# Rear_brake_lamp_v2.net
KiCad netlist of a schematic drawn in EAGLE
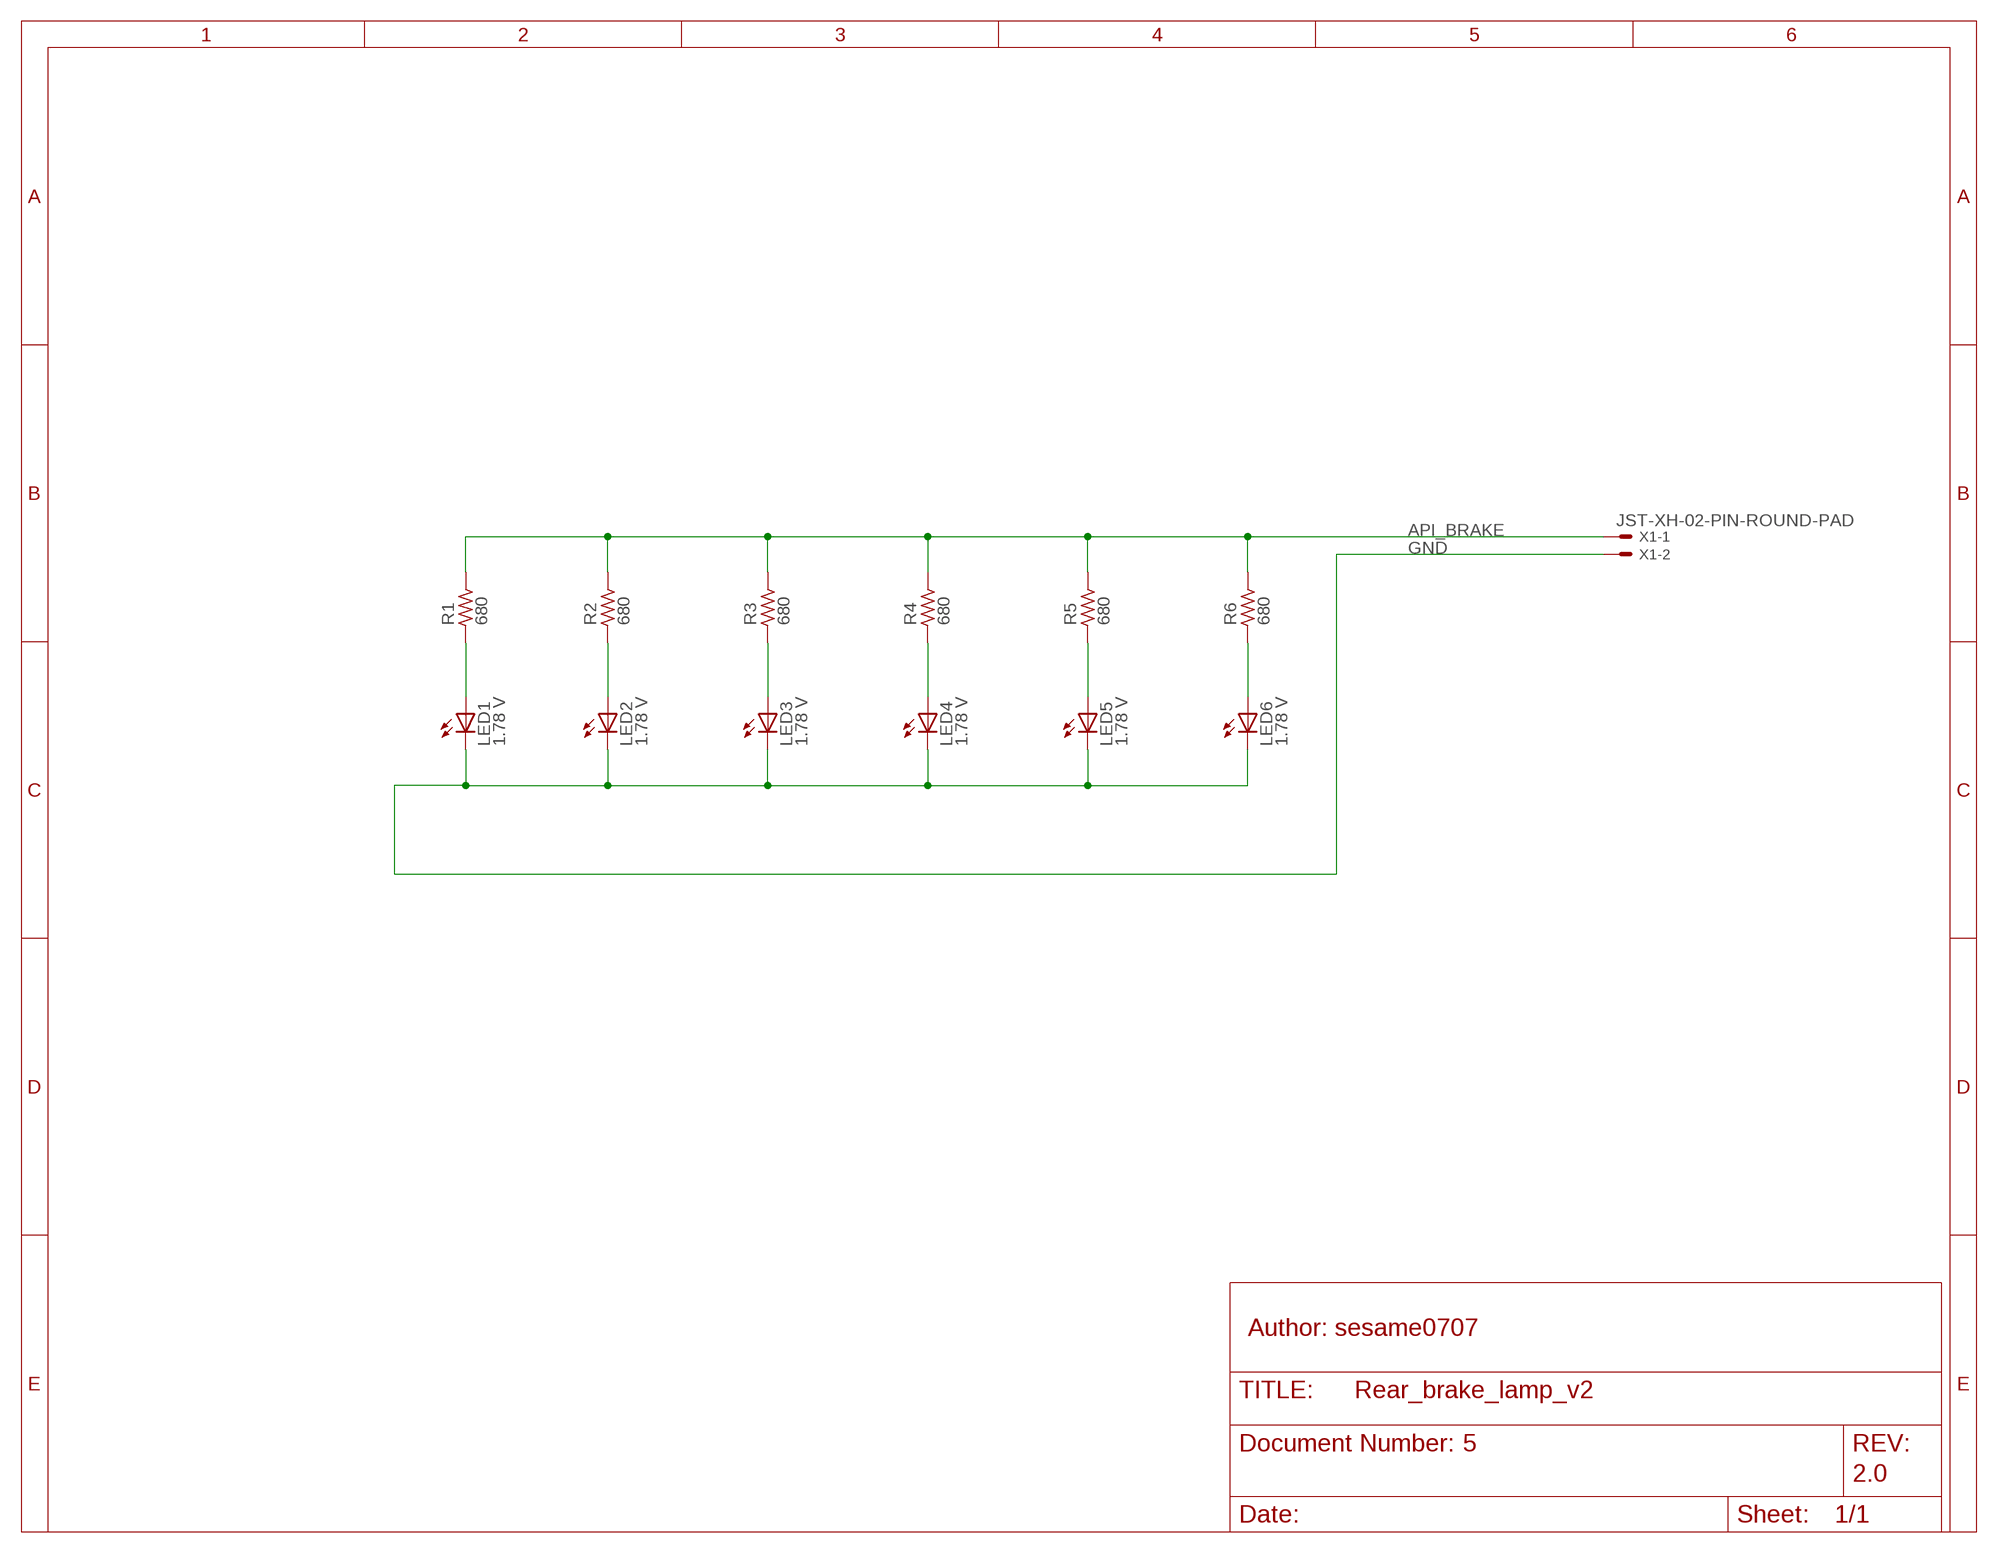
[diagram p0: schematic, sheet 1]

(export (version "E")
  (design (tool "Eeschema 10.0.6"))
  (components
    (comp (ref "LED1")
      (value "1.78 V")
      (footprint "eagle-import:LED5MM")
      (libsource (lib "eagle-import") (part "LED5MM"))
    )
    (comp (ref "LED2")
      (value "1.78 V")
      (footprint "eagle-import:LED5MM")
      (libsource (lib "eagle-import") (part "LED5MM"))
    )
    (comp (ref "LED3")
      (value "1.78 V")
      (footprint "eagle-import:LED5MM")
      (libsource (lib "eagle-import") (part "LED5MM"))
    )
    (comp (ref "LED4")
      (value "1.78 V")
      (footprint "eagle-import:LED5MM")
      (libsource (lib "eagle-import") (part "LED5MM"))
    )
    (comp (ref "LED5")
      (value "1.78 V")
      (footprint "eagle-import:LED5MM")
      (libsource (lib "eagle-import") (part "LED5MM"))
    )
    (comp (ref "LED6")
      (value "1.78 V")
      (footprint "eagle-import:LED5MM")
      (libsource (lib "eagle-import") (part "LED5MM"))
    )
    (comp (ref "R1")
      (value "680")
      (footprint "eagle-import:R0805")
      (libsource (lib "eagle-import") (part "R_0805"))
    )
    (comp (ref "R2")
      (value "680")
      (footprint "eagle-import:R0805")
      (libsource (lib "eagle-import") (part "R_0805"))
    )
    (comp (ref "R3")
      (value "680")
      (footprint "eagle-import:R0805")
      (libsource (lib "eagle-import") (part "R_0805"))
    )
    (comp (ref "R4")
      (value "680")
      (footprint "eagle-import:R0805")
      (libsource (lib "eagle-import") (part "R_0805"))
    )
    (comp (ref "R5")
      (value "680")
      (footprint "eagle-import:R0805")
      (libsource (lib "eagle-import") (part "R_0805"))
    )
    (comp (ref "R6")
      (value "680")
      (footprint "eagle-import:R0805")
      (libsource (lib "eagle-import") (part "R_0805"))
    )
    (comp (ref "X1")
      (value "JST-XH-02-PIN-ROUND-PAD")
      (footprint "eagle-import:JST-XH-02-PACKAGE-ROUND-PAD")
      (libsource (lib "eagle-import") (part "JST-XH-02-PIN-ROUND-PAD"))
    )
  )
  (nets
    (net (code "1") (name "/API_BRAKE") (class "Default")
      (node (ref "R1") (pin "2") (pinfunction "2_2") (pintype "passive"))
      (node (ref "R2") (pin "2") (pinfunction "2_2") (pintype "passive"))
      (node (ref "R3") (pin "2") (pinfunction "2_2") (pintype "passive"))
      (node (ref "R4") (pin "2") (pinfunction "2_2") (pintype "passive"))
      (node (ref "R5") (pin "2") (pinfunction "2_2") (pintype "passive"))
      (node (ref "R6") (pin "2") (pinfunction "2_2") (pintype "passive"))
      (node (ref "X1") (pin "1") (pinfunction "S_1") (pintype "passive"))
    )
    (net (code "2") (name "/GND") (class "Default")
      (node (ref "LED1") (pin "K") (pinfunction "C_K") (pintype "passive"))
      (node (ref "LED2") (pin "K") (pinfunction "C_K") (pintype "passive"))
      (node (ref "LED3") (pin "K") (pinfunction "C_K") (pintype "passive"))
      (node (ref "LED4") (pin "K") (pinfunction "C_K") (pintype "passive"))
      (node (ref "LED5") (pin "K") (pinfunction "C_K") (pintype "passive"))
      (node (ref "LED6") (pin "K") (pinfunction "C_K") (pintype "passive"))
      (node (ref "X1") (pin "2") (pinfunction "S_2") (pintype "passive"))
    )
    (net (code "3") (name "Net-(LED1-PadA)") (class "Default")
      (node (ref "LED1") (pin "A") (pinfunction "A_A") (pintype "passive"))
      (node (ref "R1") (pin "1") (pinfunction "1_1") (pintype "passive"))
    )
    (net (code "4") (name "Net-(LED2-PadA)") (class "Default")
      (node (ref "LED2") (pin "A") (pinfunction "A_A") (pintype "passive"))
      (node (ref "R2") (pin "1") (pinfunction "1_1") (pintype "passive"))
    )
    (net (code "5") (name "Net-(LED3-PadA)") (class "Default")
      (node (ref "LED3") (pin "A") (pinfunction "A_A") (pintype "passive"))
      (node (ref "R3") (pin "1") (pinfunction "1_1") (pintype "passive"))
    )
    (net (code "6") (name "Net-(LED4-PadA)") (class "Default")
      (node (ref "LED4") (pin "A") (pinfunction "A_A") (pintype "passive"))
      (node (ref "R4") (pin "1") (pinfunction "1_1") (pintype "passive"))
    )
    (net (code "7") (name "Net-(LED5-PadA)") (class "Default")
      (node (ref "LED5") (pin "A") (pinfunction "A_A") (pintype "passive"))
      (node (ref "R5") (pin "1") (pinfunction "1_1") (pintype "passive"))
    )
    (net (code "8") (name "Net-(LED6-PadA)") (class "Default")
      (node (ref "LED6") (pin "A") (pinfunction "A_A") (pintype "passive"))
      (node (ref "R6") (pin "1") (pinfunction "1_1") (pintype "passive"))
    )
  )
)
